# B_UN_C.net
KiCad netlist of a schematic drawn in Altium Designer
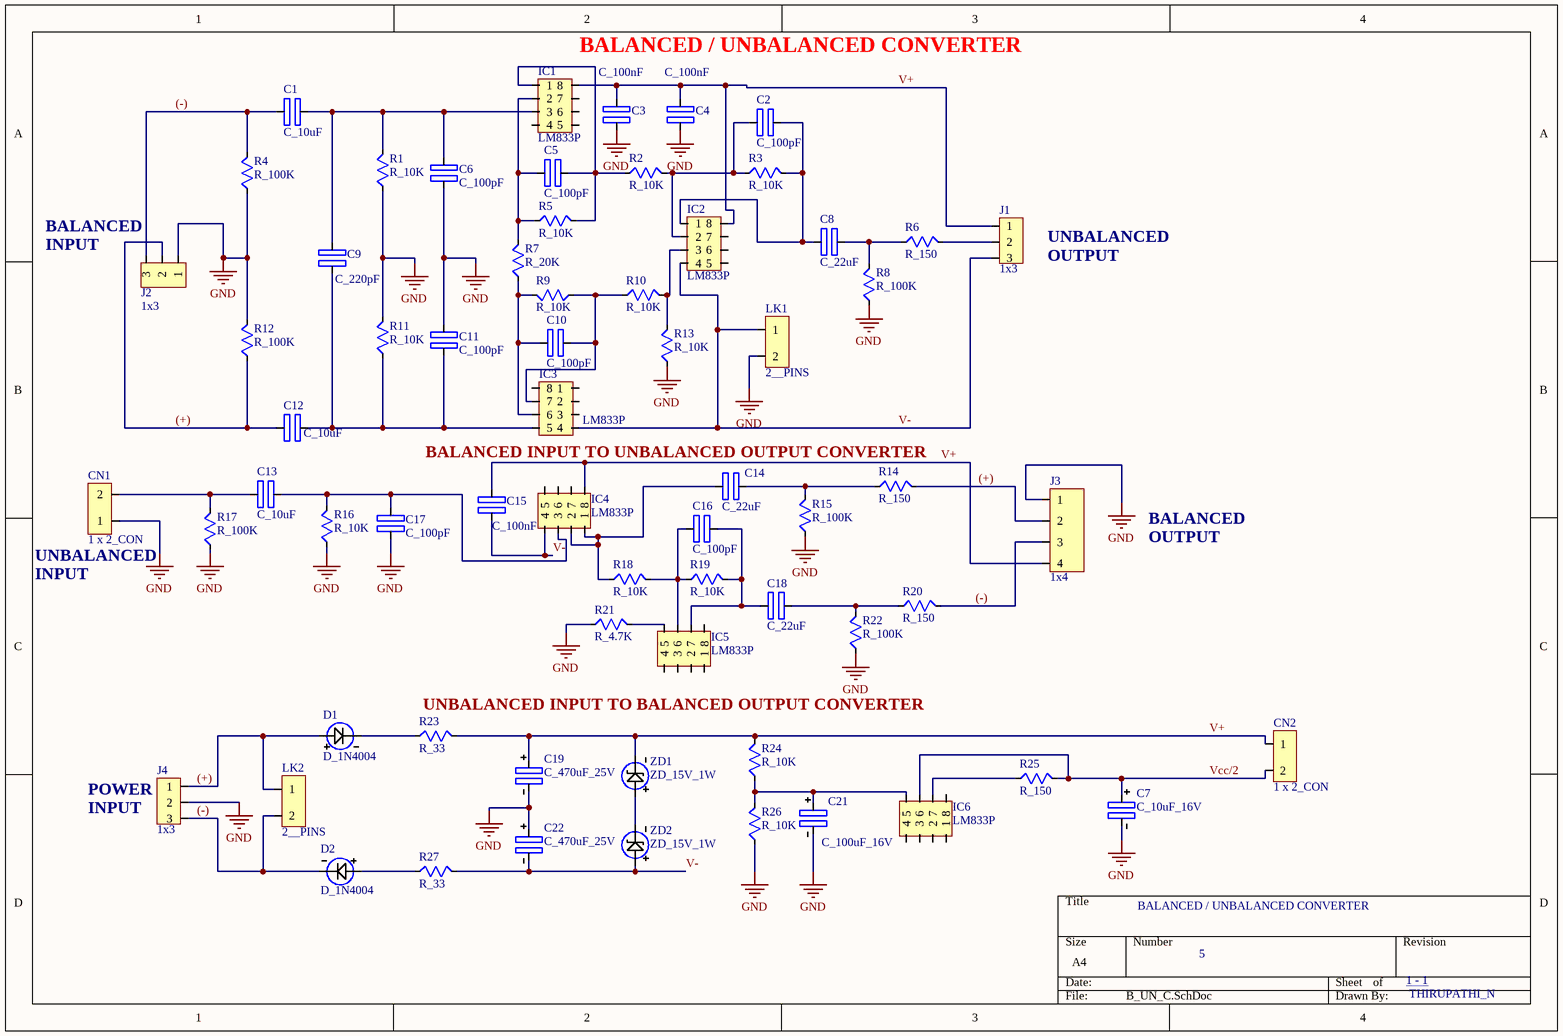
[diagram p0: B_UN_C.SchDoc]

(export (version "E")
  (design (tool "Eeschema 10.0.6"))
  (components
    (comp (ref "C1")
      (value "C_10uF")
      (footprint "C_10uF")
      (description "CAP ALUM 10UF 20% 400V RADIAL")
      (fields
        (field (name "MANUFACTURER") "Nichicon")
        (field (name "MANUFACTURER PART NUMBER") "UCA2G100MPD1TD")
      )
      (libsource (lib "Schlib1") (part "C_10uF"))
    )
    (comp (ref "C2")
      (value "C_100pF")
      (footprint "C_100pF")
      (description "CAPACITOR CERAMIC 100PF 3000V C0G 5%, RAD")
      (fields
        (field (name "MANUFACTURER") "KEMET")
        (field (name "MANUFACTURER PART NUMBER") "C330C101JHG5TA")
      )
      (libsource (lib "Schlib1") (part "C_100pF"))
    )
    (comp (ref "C3")
      (value "C_100nF")
      (footprint "C_100nF")
      (description "NICHICON   UVR2A0R1MDD1TD   ALUMINUM ELECTROLYTIC CAPACITOR, 0.1UF, 100V, 20%, RADIAL")
      (fields
        (field (name "MANUFACTURER") "Nichicon")
        (field (name "MANUFACTURER PART NUMBER") "UVR2A0R1MDD1TD")
      )
      (libsource (lib "Schlib1") (part "C_100nF"))
    )
    (comp (ref "C4")
      (value "C_100nF")
      (footprint "C_100nF")
      (description "NICHICON   UVR2A0R1MDD1TD   ALUMINUM ELECTROLYTIC CAPACITOR, 0.1UF, 100V, 20%, RADIAL")
      (fields
        (field (name "MANUFACTURER") "Nichicon")
        (field (name "MANUFACTURER PART NUMBER") "UVR2A0R1MDD1TD")
      )
      (libsource (lib "Schlib1") (part "C_100nF"))
    )
    (comp (ref "C5")
      (value "C_100pF")
      (footprint "C_100pF")
      (description "CAPACITOR CERAMIC 100PF 3000V C0G 5%, RAD")
      (fields
        (field (name "MANUFACTURER") "KEMET")
        (field (name "MANUFACTURER PART NUMBER") "C330C101JHG5TA")
      )
      (libsource (lib "Schlib1") (part "C_100pF"))
    )
    (comp (ref "C6")
      (value "C_100pF")
      (footprint "C_100pF")
      (description "CAPACITOR CERAMIC 100PF 3000V C0G 5%, RAD")
      (fields
        (field (name "MANUFACTURER") "KEMET")
        (field (name "MANUFACTURER PART NUMBER") "C330C101JHG5TA")
      )
      (libsource (lib "Schlib1") (part "C_100pF"))
    )
    (comp (ref "C7")
      (value "C_10uF_16V")
      (footprint "C_10uF_16V")
      (description "CAPACITOR ALUM ELECT, 10UF, 16V, 20%, RADIAL")
      (fields
        (field (name "MANUFACTURER") "Nichicon")
        (field (name "MANUFACTURER PART NUMBER") "UST1C100MDD1TE")
      )
      (libsource (lib "Schlib1") (part "C_10uF_16V"))
    )
    (comp (ref "C8")
      (value "C_22uF")
      (footprint "C_22uF")
      (description "Cap Aluminum Lytic 22uF 50V 20% (5 X 11mm) Radial 2.5mm 95mA 2000h 85C Ammo Pack")
      (fields
        (field (name "MANUFACTURER") "Nichicon")
        (field (name "MANUFACTURER PART NUMBER") "UVR1H220MDD1TD")
      )
      (libsource (lib "Schlib1") (part "C_22uF"))
    )
    (comp (ref "C9")
      (value "C_220pF")
      (footprint "C_220pF")
      (fields
        (field (name "MANUFACTURER") "Vishay BCcomponents")
        (field (name "MANUFACTURER PART NUMBER") "F221K25Y5RN6UK5R")
        (field (name "TOLERANCE") "10%")
      )
      (libsource (lib "Schlib1") (part "C_220pF"))
    )
    (comp (ref "C10")
      (value "C_100pF")
      (footprint "C_100pF")
      (description "CAPACITOR CERAMIC 100PF 3000V C0G 5%, RAD")
      (fields
        (field (name "MANUFACTURER") "KEMET")
        (field (name "MANUFACTURER PART NUMBER") "C330C101JHG5TA")
      )
      (libsource (lib "Schlib1") (part "C_100pF"))
    )
    (comp (ref "C11")
      (value "C_100pF")
      (footprint "C_100pF")
      (description "CAPACITOR CERAMIC 100PF 3000V C0G 5%, RAD")
      (fields
        (field (name "MANUFACTURER") "KEMET")
        (field (name "MANUFACTURER PART NUMBER") "C330C101JHG5TA")
      )
      (libsource (lib "Schlib1") (part "C_100pF"))
    )
    (comp (ref "C12")
      (value "C_10uF")
      (footprint "C_10uF")
      (description "CAP ALUM 10UF 20% 400V RADIAL")
      (fields
        (field (name "MANUFACTURER") "Nichicon")
        (field (name "MANUFACTURER PART NUMBER") "UCA2G100MPD1TD")
      )
      (libsource (lib "Schlib1") (part "C_10uF"))
    )
    (comp (ref "C13")
      (value "C_10uF")
      (footprint "C_10uF")
      (description "CAP ALUM 10UF 20% 400V RADIAL")
      (fields
        (field (name "MANUFACTURER") "Nichicon")
        (field (name "MANUFACTURER PART NUMBER") "UCA2G100MPD1TD")
      )
      (libsource (lib "Schlib1") (part "C_10uF"))
    )
    (comp (ref "C14")
      (value "C_22uF")
      (footprint "C_22uF")
      (description "Cap Aluminum Lytic 22uF 50V 20% (5 X 11mm) Radial 2.5mm 95mA 2000h 85C Ammo Pack")
      (fields
        (field (name "MANUFACTURER") "Nichicon")
        (field (name "MANUFACTURER PART NUMBER") "UVR1H220MDD1TD")
      )
      (libsource (lib "Schlib1") (part "C_22uF"))
    )
    (comp (ref "C15")
      (value "C_100nF")
      (footprint "C_100nF")
      (description "NICHICON   UVR2A0R1MDD1TD   ALUMINUM ELECTROLYTIC CAPACITOR, 0.1UF, 100V, 20%, RADIAL")
      (fields
        (field (name "MANUFACTURER") "Nichicon")
        (field (name "MANUFACTURER PART NUMBER") "UVR2A0R1MDD1TD")
      )
      (libsource (lib "Schlib1") (part "C_100nF"))
    )
    (comp (ref "C16")
      (value "C_100pF")
      (footprint "C_100pF")
      (description "CAPACITOR CERAMIC 100PF 3000V C0G 5%, RAD")
      (fields
        (field (name "MANUFACTURER") "KEMET")
        (field (name "MANUFACTURER PART NUMBER") "C330C101JHG5TA")
      )
      (libsource (lib "Schlib1") (part "C_100pF"))
    )
    (comp (ref "C17")
      (value "C_100pF")
      (footprint "C_100pF")
      (description "CAPACITOR CERAMIC 100PF 3000V C0G 5%, RAD")
      (fields
        (field (name "MANUFACTURER") "KEMET")
        (field (name "MANUFACTURER PART NUMBER") "C330C101JHG5TA")
      )
      (libsource (lib "Schlib1") (part "C_100pF"))
    )
    (comp (ref "C18")
      (value "C_22uF")
      (footprint "C_22uF")
      (description "Cap Aluminum Lytic 22uF 50V 20% (5 X 11mm) Radial 2.5mm 95mA 2000h 85C Ammo Pack")
      (fields
        (field (name "MANUFACTURER") "Nichicon")
        (field (name "MANUFACTURER PART NUMBER") "UVR1H220MDD1TD")
      )
      (libsource (lib "Schlib1") (part "C_22uF"))
    )
    (comp (ref "C19")
      (value "C_470uF_25V")
      (footprint "C_25V_470uF")
      (fields
        (field (name "MANUFACTURER") "Nichicon")
        (field (name "MANUFACTURER PART NUMBER") "UHE1E471MPD6TD")
        (field (name "TOLERANCE") "20%")
      )
      (libsource (lib "Schlib1") (part "C_470uF_25V"))
    )
    (comp (ref "C21")
      (value "C_100uF_16V")
      (footprint "C_100uF_16V")
      (description "Cap Aluminum Lytic 100uF 16V 20% (6.3 X 7mm) Radial 2.5mm 110mA 1000h 105°C Ammo")
      (fields
        (field (name "MANUFACTURER") "KEMET")
        (field (name "MANUFACTURER PART NUMBER") "ESS107M016AE2EA")
      )
      (libsource (lib "Schlib1") (part "C_100uF_16V"))
    )
    (comp (ref "C22")
      (value "C_470uF_25V")
      (footprint "C_25V_470uF")
      (fields
        (field (name "MANUFACTURER") "Nichicon")
        (field (name "MANUFACTURER PART NUMBER") "UHE1E471MPD6TD")
        (field (name "TOLERANCE") "20%")
      )
      (libsource (lib "Schlib1") (part "C_470uF_25V"))
    )
    (comp (ref "CN1")
      (value "1 x 2_CON")
      (footprint "1*2_CONNECTOR")
      (description "TERM BLK 2POS SIDE ENTRY 5MM PCB")
      (fields
        (field (name "MANUFACTURER") "Wurth Electronics")
        (field (name "MANUFACTURER PART NUMBER") "691137710002")
      )
      (libsource (lib "") (part "1 x 2_CON_1"))
    )
    (comp (ref "CN2")
      (value "1 x 2_CON")
      (footprint "1*2_CONNECTOR")
      (description "TERM BLK 2POS SIDE ENTRY 5MM PCB")
      (fields
        (field (name "MANUFACTURER") "Wurth Electronics")
        (field (name "MANUFACTURER PART NUMBER") "691137710002")
      )
      (libsource (lib "Schlib1") (part "1 x 2_CON"))
    )
    (comp (ref "D1")
      (value "D_1N4004")
      (footprint "D_IN4004")
      (description "DIODES INC. - 1N4004-T - Standard Recovery Diode, 400 V, 1 A, Single, 1 V, 30 A")
      (fields (field (name "MANUFACTURER") "Diodes") (field (name "MANUFACTURER PART NUMBER") "1N4004-T"))
      (libsource (lib "Schlib1") (part "D_1N4004"))
    )
    (comp (ref "D2")
      (value "D_1N4004")
      (footprint "D_IN4004")
      (description "DIODES INC. - 1N4004-T - Standard Recovery Diode, 400 V, 1 A, Single, 1 V, 30 A")
      (fields (field (name "MANUFACTURER") "Diodes") (field (name "MANUFACTURER PART NUMBER") "1N4004-T"))
      (libsource (lib "Schlib1") (part "D_1N4004"))
    )
    (comp (ref "IC1")
      (value "LM833P")
      (footprint "IC_833")
      (description "OP Amp Dual GP 18V/36V 8-Pin PDIP Tube")
      (fields (field (name "MANUFACTURER") "Texas Instruments"))
      (libsource (lib "Schlib1") (part "LM833P"))
    )
    (comp (ref "IC2")
      (value "LM833P")
      (footprint "IC_833")
      (description "OP Amp Dual GP 18V/36V 8-Pin PDIP Tube")
      (fields (field (name "MANUFACTURER") "Texas Instruments"))
      (libsource (lib "Schlib1") (part "LM833P"))
    )
    (comp (ref "IC3")
      (value "LM833P")
      (footprint "IC_833")
      (description "OP Amp Dual GP 18V/36V 8-Pin PDIP Tube")
      (fields (field (name "MANUFACTURER") "Texas Instruments"))
      (libsource (lib "") (part "LM833P_1"))
    )
    (comp (ref "IC4")
      (value "LM833P")
      (footprint "IC_833")
      (description "OP Amp Dual GP 18V/36V 8-Pin PDIP Tube")
      (fields (field (name "MANUFACTURER") "Texas Instruments"))
      (libsource (lib "Schlib1") (part "LM833P"))
    )
    (comp (ref "IC5")
      (value "LM833P")
      (footprint "IC_833")
      (description "OP Amp Dual GP 18V/36V 8-Pin PDIP Tube")
      (fields (field (name "MANUFACTURER") "Texas Instruments"))
      (libsource (lib "Schlib1") (part "LM833P"))
    )
    (comp (ref "IC6")
      (value "LM833P")
      (footprint "IC_833")
      (description "OP Amp Dual GP 18V/36V 8-Pin PDIP Tube")
      (fields (field (name "MANUFACTURER") "Texas Instruments"))
      (libsource (lib "Schlib1") (part "LM833P"))
    )
    (comp (ref "J1")
      (value "1x3")
      (footprint "1*3_CONNECTOR")
      (description "Fixed Terminal Blocks WR-TBL SMT Model7097 3Pin 5mm Hztl")
      (fields
        (field (name "MANUFACTURER") "Wurth Electronics Midcom")
        (field (name "MANUFACTURER PART NUMBER") "691709710303")
      )
      (libsource (lib "Schlib1") (part "1x3"))
    )
    (comp (ref "J2")
      (value "1x3")
      (footprint "1*3_CONNECTOR")
      (description "Fixed Terminal Blocks WR-TBL SMT Model7097 3Pin 5mm Hztl")
      (fields
        (field (name "MANUFACTURER") "Wurth Electronics Midcom")
        (field (name "MANUFACTURER PART NUMBER") "691709710303")
      )
      (libsource (lib "") (part "1x3_1"))
    )
    (comp (ref "J3")
      (value "1x4")
      (footprint "1*4_CONNECTOR")
      (description "TERM BLK 4POS SIDE ENTRY 5MM PCB")
      (fields
        (field (name "MANUFACTURER") "Wurth Electronics")
        (field (name "MANUFACTURER PART NUMBER") "691137710004")
      )
      (libsource (lib "Schlib1") (part "1x4"))
    )
    (comp (ref "J4")
      (value "1x3")
      (footprint "1*3_CONNECTOR")
      (description "Fixed Terminal Blocks WR-TBL SMT Model7097 3Pin 5mm Hztl")
      (fields
        (field (name "MANUFACTURER") "Wurth Electronics Midcom")
        (field (name "MANUFACTURER PART NUMBER") "691709710303")
      )
      (libsource (lib "") (part "1x3_1"))
    )
    (comp (ref "LK1")
      (value "2__PINS")
      (footprint "2_PIN")
      (description "HARWIN - M20-9990246 - CONNECTOR, HEADER, 2 POSITION, 1ROW, 2.54MM")
      (fields (field (name "MANUFACTURER") "Harwin") (field (name "MANUFACTURER PART NUMBER") "M20-9990246"))
      (libsource (lib "Schlib1") (part "2__PINS"))
    )
    (comp (ref "LK2")
      (value "2__PINS")
      (footprint "2_PIN")
      (description "HARWIN - M20-9990246 - CONNECTOR, HEADER, 2 POSITION, 1ROW, 2.54MM")
      (fields (field (name "MANUFACTURER") "Harwin") (field (name "MANUFACTURER PART NUMBER") "M20-9990246"))
      (libsource (lib "Schlib1") (part "2__PINS"))
    )
    (comp (ref "R1")
      (value "R_10K")
      (footprint "CF_RESISTOR_FP")
      (description "RES 10K OHM 1/4W 5% AXIAL")
      (fields
        (field (name "MANUFACTURER") "Stackpole Electronics")
        (field (name "MANUFACTURER PART NUMBER") "CF14JT10K0")
      )
      (libsource (lib "Schlib1") (part "R_10K"))
    )
    (comp (ref "R2")
      (value "R_10K")
      (footprint "CF_RESISTOR_FP")
      (description "RES 10K OHM 1/4W 5% AXIAL")
      (fields
        (field (name "MANUFACTURER") "Stackpole Electronics")
        (field (name "MANUFACTURER PART NUMBER") "CF14JT10K0")
      )
      (libsource (lib "Schlib1") (part "R_10K"))
    )
    (comp (ref "R3")
      (value "R_10K")
      (footprint "CF_RESISTOR_FP")
      (description "RES 10K OHM 1/4W 5% AXIAL")
      (fields
        (field (name "MANUFACTURER") "Stackpole Electronics")
        (field (name "MANUFACTURER PART NUMBER") "CF14JT10K0")
      )
      (libsource (lib "Schlib1") (part "R_10K"))
    )
    (comp (ref "R4")
      (value "R_100K")
      (footprint "CF_RESISTOR_FP")
      (description "RES 100K OHM 1/4W 5% AXIAL")
      (fields
        (field (name "MANUFACTURER") "Stackpole Electronics")
        (field (name "MANUFACTURER PART NUMBER") "CF14JT100K")
      )
      (libsource (lib "Schlib1") (part "R_100K"))
    )
    (comp (ref "R5")
      (value "R_10K")
      (footprint "CF_RESISTOR_FP")
      (description "RES 10K OHM 1/4W 5% AXIAL")
      (fields
        (field (name "MANUFACTURER") "Stackpole Electronics")
        (field (name "MANUFACTURER PART NUMBER") "CF14JT10K0")
      )
      (libsource (lib "Schlib1") (part "R_10K"))
    )
    (comp (ref "R6")
      (value "R_150")
      (footprint "CF_RESISTOR_FP")
      (description "Res Carbon Film 150 Ohm 5% 1/4W -400ppm/C to 0ppm/C Conformal AXL Thru-Hole T/R")
      (fields
        (field (name "MANUFACTURER") "Stackpole Electronics")
        (field (name "MANUFACTURER PART NUMBER") "CF14JT150R")
      )
      (libsource (lib "Schlib1") (part "R_150"))
    )
    (comp (ref "R7")
      (value "R_20K")
      (footprint "CF_RESISTOR_FP")
      (description "RES 20K OHM 1/2W 5% AXIAL")
      (fields
        (field (name "MANUFACTURER") "Stackpole Electronics")
        (field (name "MANUFACTURER PART NUMBER") "CF12JT20K0")
      )
      (libsource (lib "Schlib1") (part "R_20K"))
    )
    (comp (ref "R8")
      (value "R_100K")
      (footprint "CF_RESISTOR_FP")
      (description "RES 100K OHM 1/4W 5% AXIAL")
      (fields
        (field (name "MANUFACTURER") "Stackpole Electronics")
        (field (name "MANUFACTURER PART NUMBER") "CF14JT100K")
      )
      (libsource (lib "Schlib1") (part "R_100K"))
    )
    (comp (ref "R9")
      (value "R_10K")
      (footprint "CF_RESISTOR_FP")
      (description "RES 10K OHM 1/4W 5% AXIAL")
      (fields
        (field (name "MANUFACTURER") "Stackpole Electronics")
        (field (name "MANUFACTURER PART NUMBER") "CF14JT10K0")
      )
      (libsource (lib "Schlib1") (part "R_10K"))
    )
    (comp (ref "R10")
      (value "R_10K")
      (footprint "CF_RESISTOR_FP")
      (description "RES 10K OHM 1/4W 5% AXIAL")
      (fields
        (field (name "MANUFACTURER") "Stackpole Electronics")
        (field (name "MANUFACTURER PART NUMBER") "CF14JT10K0")
      )
      (libsource (lib "Schlib1") (part "R_10K"))
    )
    (comp (ref "R11")
      (value "R_10K")
      (footprint "CF_RESISTOR_FP")
      (description "RES 10K OHM 1/4W 5% AXIAL")
      (fields
        (field (name "MANUFACTURER") "Stackpole Electronics")
        (field (name "MANUFACTURER PART NUMBER") "CF14JT10K0")
      )
      (libsource (lib "Schlib1") (part "R_10K"))
    )
    (comp (ref "R12")
      (value "R_100K")
      (footprint "CF_RESISTOR_FP")
      (description "RES 100K OHM 1/4W 5% AXIAL")
      (fields
        (field (name "MANUFACTURER") "Stackpole Electronics")
        (field (name "MANUFACTURER PART NUMBER") "CF14JT100K")
      )
      (libsource (lib "Schlib1") (part "R_100K"))
    )
    (comp (ref "R13")
      (value "R_10K")
      (footprint "CF_RESISTOR_FP")
      (description "RES 10K OHM 1/4W 5% AXIAL")
      (fields
        (field (name "MANUFACTURER") "Stackpole Electronics")
        (field (name "MANUFACTURER PART NUMBER") "CF14JT10K0")
      )
      (libsource (lib "Schlib1") (part "R_10K"))
    )
    (comp (ref "R14")
      (value "R_150")
      (footprint "CF_RESISTOR_FP")
      (description "Res Carbon Film 150 Ohm 5% 1/4W -400ppm/C to 0ppm/C Conformal AXL Thru-Hole T/R")
      (fields
        (field (name "MANUFACTURER") "Stackpole Electronics")
        (field (name "MANUFACTURER PART NUMBER") "CF14JT150R")
      )
      (libsource (lib "Schlib1") (part "R_150"))
    )
    (comp (ref "R15")
      (value "R_100K")
      (footprint "CF_RESISTOR_FP")
      (description "RES 100K OHM 1/4W 5% AXIAL")
      (fields
        (field (name "MANUFACTURER") "Stackpole Electronics")
        (field (name "MANUFACTURER PART NUMBER") "CF14JT100K")
      )
      (libsource (lib "Schlib1") (part "R_100K"))
    )
    (comp (ref "R16")
      (value "R_10K")
      (footprint "CF_RESISTOR_FP")
      (description "RES 10K OHM 1/4W 5% AXIAL")
      (fields
        (field (name "MANUFACTURER") "Stackpole Electronics")
        (field (name "MANUFACTURER PART NUMBER") "CF14JT10K0")
      )
      (libsource (lib "Schlib1") (part "R_10K"))
    )
    (comp (ref "R17")
      (value "R_100K")
      (footprint "CF_RESISTOR_FP")
      (description "RES 100K OHM 1/4W 5% AXIAL")
      (fields
        (field (name "MANUFACTURER") "Stackpole Electronics")
        (field (name "MANUFACTURER PART NUMBER") "CF14JT100K")
      )
      (libsource (lib "Schlib1") (part "R_100K"))
    )
    (comp (ref "R18")
      (value "R_10K")
      (footprint "CF_RESISTOR_FP")
      (description "RES 10K OHM 1/4W 5% AXIAL")
      (fields
        (field (name "MANUFACTURER") "Stackpole Electronics")
        (field (name "MANUFACTURER PART NUMBER") "CF14JT10K0")
      )
      (libsource (lib "Schlib1") (part "R_10K"))
    )
    (comp (ref "R19")
      (value "R_10K")
      (footprint "CF_RESISTOR_FP")
      (description "RES 10K OHM 1/4W 5% AXIAL")
      (fields
        (field (name "MANUFACTURER") "Stackpole Electronics")
        (field (name "MANUFACTURER PART NUMBER") "CF14JT10K0")
      )
      (libsource (lib "Schlib1") (part "R_10K"))
    )
    (comp (ref "R20")
      (value "R_150")
      (footprint "CF_RESISTOR_FP")
      (description "Res Carbon Film 150 Ohm 5% 1/4W -400ppm/C to 0ppm/C Conformal AXL Thru-Hole T/R")
      (fields
        (field (name "MANUFACTURER") "Stackpole Electronics")
        (field (name "MANUFACTURER PART NUMBER") "CF14JT150R")
      )
      (libsource (lib "Schlib1") (part "R_150"))
    )
    (comp (ref "R21")
      (value "R_4.7K")
      (footprint "R_4.7K")
      (fields
        (field (name "MANUFACTURER") "Ohmite")
        (field (name "MANUFACTURER PART NUMBER") "OY472KE")
        (field (name "TOLERANCE") "10%")
      )
      (libsource (lib "Schlib1") (part "R_4.7K"))
    )
    (comp (ref "R22")
      (value "R_100K")
      (footprint "CF_RESISTOR_FP")
      (description "RES 100K OHM 1/4W 5% AXIAL")
      (fields
        (field (name "MANUFACTURER") "Stackpole Electronics")
        (field (name "MANUFACTURER PART NUMBER") "CF14JT100K")
      )
      (libsource (lib "Schlib1") (part "R_100K"))
    )
    (comp (ref "R23")
      (value "R_33")
      (footprint "CF_RESISTOR_FP")
      (description "RES 33 OHM 1/2W 5% AXIAL")
      (fields
        (field (name "MANUFACTURER") "Stackpole Electronics")
        (field (name "MANUFACTURER PART NUMBER") "CF12JT33R0")
      )
      (libsource (lib "Schlib1") (part "R_33"))
    )
    (comp (ref "R24")
      (value "R_10K")
      (footprint "CF_RESISTOR_FP")
      (description "RES 10K OHM 1/4W 5% AXIAL")
      (fields
        (field (name "MANUFACTURER") "Stackpole Electronics")
        (field (name "MANUFACTURER PART NUMBER") "CF14JT10K0")
      )
      (libsource (lib "Schlib1") (part "R_10K"))
    )
    (comp (ref "R25")
      (value "R_150")
      (footprint "CF_RESISTOR_FP")
      (description "Res Carbon Film 150 Ohm 5% 1/4W -400ppm/C to 0ppm/C Conformal AXL Thru-Hole T/R")
      (fields
        (field (name "MANUFACTURER") "Stackpole Electronics")
        (field (name "MANUFACTURER PART NUMBER") "CF14JT150R")
      )
      (libsource (lib "Schlib1") (part "R_150"))
    )
    (comp (ref "R26")
      (value "R_10K")
      (footprint "CF_RESISTOR_FP")
      (description "RES 10K OHM 1/4W 5% AXIAL")
      (fields
        (field (name "MANUFACTURER") "Stackpole Electronics")
        (field (name "MANUFACTURER PART NUMBER") "CF14JT10K0")
      )
      (libsource (lib "Schlib1") (part "R_10K"))
    )
    (comp (ref "R27")
      (value "R_33")
      (footprint "CF_RESISTOR_FP")
      (description "RES 33 OHM 1/2W 5% AXIAL")
      (fields
        (field (name "MANUFACTURER") "Stackpole Electronics")
        (field (name "MANUFACTURER PART NUMBER") "CF12JT33R0")
      )
      (libsource (lib "Schlib1") (part "R_33"))
    )
    (comp (ref "ZD1")
      (value "ZD_15V_1W")
      (footprint "ZR_15V_1W")
      (description "GLOVE, POLYAMIDE, L/FREE, PU, SIZE 6 - More Details")
      (fields
        (field (name "MANUFACTURER") "NXP Semiconductors")
        (field (name "MANUFACTURER PART NUMBER") "BZV85-C15,113")
      )
      (libsource (lib "Schlib1") (part "ZD_15V_1W"))
    )
    (comp (ref "ZD2")
      (value "ZD_15V_1W")
      (footprint "ZR_15V_1W")
      (description "GLOVE, POLYAMIDE, L/FREE, PU, SIZE 6 - More Details")
      (fields
        (field (name "MANUFACTURER") "NXP Semiconductors")
        (field (name "MANUFACTURER PART NUMBER") "BZV85-C15,113")
      )
      (libsource (lib "Schlib1") (part "ZD_15V_1W"))
    )
  )
  (nets
    (net (code "1") (name "/(+)") (class "Default")
      (node (ref "C12") (pin "0") (pinfunction "0_0") (pintype "passive"))
      (node (ref "D1") (pin "2") (pinfunction "2_2") (pintype "passive"))
      (node (ref "J2") (pin "2") (pinfunction "2_2") (pintype "passive"))
      (node (ref "J3") (pin "2") (pinfunction "2_2") (pintype "passive"))
      (node (ref "J4") (pin "1") (pinfunction "1_1") (pintype "passive"))
      (node (ref "LK2") (pin "1") (pinfunction "1_1") (pintype "passive"))
      (node (ref "R12") (pin "0") (pinfunction "0_0") (pintype "passive"))
      (node (ref "R14") (pin "1") (pinfunction "1_1") (pintype "passive"))
    )
    (net (code "2") (name "/(-)") (class "Default")
      (node (ref "C1") (pin "0") (pinfunction "0_0") (pintype "passive"))
      (node (ref "D2") (pin "1") (pinfunction "1_1") (pintype "passive"))
      (node (ref "J2") (pin "3") (pinfunction "3_3") (pintype "passive"))
      (node (ref "J3") (pin "3") (pinfunction "3_3") (pintype "passive"))
      (node (ref "J4") (pin "3") (pinfunction "3_3") (pintype "passive"))
      (node (ref "LK2") (pin "2") (pinfunction "2_2") (pintype "passive"))
      (node (ref "R20") (pin "1") (pinfunction "1_1") (pintype "passive"))
      (node (ref "R4") (pin "1") (pinfunction "1_1") (pintype "passive"))
    )
    (net (code "3") (name "/V+") (class "Default")
      (node (ref "C15") (pin "1") (pinfunction "1_1") (pintype "passive"))
      (node (ref "C19") (pin "0") (pinfunction "0_0") (pintype "passive"))
      (node (ref "C3") (pin "1") (pinfunction "1_1") (pintype "passive"))
      (node (ref "C4") (pin "1") (pinfunction "1_1") (pintype "passive"))
      (node (ref "CN2") (pin "1") (pinfunction "1_1") (pintype "passive"))
      (node (ref "IC1") (pin "8") (pinfunction "8_8") (pintype "passive"))
      (node (ref "IC2") (pin "8") (pinfunction "8_8") (pintype "passive"))
      (node (ref "IC4") (pin "8") (pinfunction "8_8") (pintype "passive"))
      (node (ref "J1") (pin "1") (pinfunction "1_1") (pintype "passive"))
      (node (ref "J3") (pin "4") (pinfunction "4_4") (pintype "passive"))
      (node (ref "R23") (pin "1") (pinfunction "1_1") (pintype "passive"))
      (node (ref "R24") (pin "1") (pinfunction "1_1") (pintype "passive"))
      (node (ref "ZD1") (pin "1") (pinfunction "1_1") (pintype "passive"))
    )
    (net (code "4") (name "/V-") (class "Default")
      (node (ref "C15") (pin "0") (pinfunction "0_0") (pintype "passive"))
      (node (ref "C22") (pin "1") (pinfunction "1_1") (pintype "passive"))
      (node (ref "IC2") (pin "4") (pinfunction "4_4") (pintype "passive"))
      (node (ref "IC3") (pin "4") (pinfunction "4_4") (pintype "passive"))
      (node (ref "IC4") (pin "4") (pinfunction "4_4") (pintype "passive"))
      (node (ref "J1") (pin "3") (pinfunction "3_3") (pintype "passive"))
      (node (ref "LK1") (pin "1") (pinfunction "1_1") (pintype "passive"))
      (node (ref "R27") (pin "1") (pinfunction "1_1") (pintype "passive"))
      (node (ref "ZD2") (pin "2") (pinfunction "2_2") (pintype "passive"))
    )
    (net (code "5") (name "/Vcc{slash}2") (class "Default")
      (node (ref "C7") (pin "0") (pinfunction "0_0") (pintype "passive"))
      (node (ref "CN2") (pin "2") (pinfunction "2_2") (pintype "passive"))
      (node (ref "IC6") (pin "6") (pinfunction "6_6") (pintype "passive"))
      (node (ref "R25") (pin "1") (pinfunction "1_1") (pintype "passive"))
    )
    (net (code "6") (name "GND") (class "Default")
      (node (ref "C11") (pin "1") (pinfunction "1_1") (pintype "passive"))
      (node (ref "C17") (pin "0") (pinfunction "0_0") (pintype "passive"))
      (node (ref "C19") (pin "1") (pinfunction "1_1") (pintype "passive"))
      (node (ref "C21") (pin "1") (pinfunction "1_1") (pintype "passive"))
      (node (ref "C22") (pin "0") (pinfunction "0_0") (pintype "passive"))
      (node (ref "C3") (pin "0") (pinfunction "0_0") (pintype "passive"))
      (node (ref "C4") (pin "0") (pinfunction "0_0") (pintype "passive"))
      (node (ref "C6") (pin "0") (pinfunction "0_0") (pintype "passive"))
      (node (ref "C7") (pin "1") (pinfunction "1_1") (pintype "passive"))
      (node (ref "CN1") (pin "1") (pinfunction "1_1") (pintype "passive"))
      (node (ref "J2") (pin "1") (pinfunction "1_1") (pintype "passive"))
      (node (ref "J3") (pin "1") (pinfunction "1_1") (pintype "passive"))
      (node (ref "J4") (pin "2") (pinfunction "2_2") (pintype "passive"))
      (node (ref "LK1") (pin "2") (pinfunction "2_2") (pintype "passive"))
      (node (ref "R1") (pin "0") (pinfunction "0_0") (pintype "passive"))
      (node (ref "R11") (pin "1") (pinfunction "1_1") (pintype "passive"))
      (node (ref "R12") (pin "1") (pinfunction "1_1") (pintype "passive"))
      (node (ref "R13") (pin "0") (pinfunction "0_0") (pintype "passive"))
      (node (ref "R15") (pin "0") (pinfunction "0_0") (pintype "passive"))
      (node (ref "R16") (pin "0") (pinfunction "0_0") (pintype "passive"))
      (node (ref "R17") (pin "0") (pinfunction "0_0") (pintype "passive"))
      (node (ref "R21") (pin "0") (pinfunction "0_0") (pintype "passive"))
      (node (ref "R22") (pin "0") (pinfunction "0_0") (pintype "passive"))
      (node (ref "R26") (pin "0") (pinfunction "0_0") (pintype "passive"))
      (node (ref "R4") (pin "0") (pinfunction "0_0") (pintype "passive"))
      (node (ref "R8") (pin "0") (pinfunction "0_0") (pintype "passive"))
    )
    (net (code "7") (name "Net-(C1-Pad1)") (class "Default")
      (node (ref "C1") (pin "1") (pinfunction "1_1") (pintype "passive"))
      (node (ref "C6") (pin "1") (pinfunction "1_1") (pintype "passive"))
      (node (ref "C9") (pin "1") (pinfunction "1_1") (pintype "passive"))
      (node (ref "IC1") (pin "3") (pinfunction "3_3") (pintype "passive"))
      (node (ref "R1") (pin "1") (pinfunction "1_1") (pintype "passive"))
    )
    (net (code "8") (name "Net-(C2-Pad0)") (class "Default")
      (node (ref "C2") (pin "0") (pinfunction "0_0") (pintype "passive"))
      (node (ref "IC2") (pin "2") (pinfunction "2_2") (pintype "passive"))
      (node (ref "R2") (pin "1") (pinfunction "1_1") (pintype "passive"))
      (node (ref "R3") (pin "0") (pinfunction "0_0") (pintype "passive"))
    )
    (net (code "9") (name "Net-(C2-Pad1)") (class "Default")
      (node (ref "C2") (pin "1") (pinfunction "1_1") (pintype "passive"))
      (node (ref "C8") (pin "0") (pinfunction "0_0") (pintype "passive"))
      (node (ref "IC2") (pin "1") (pinfunction "1_1") (pintype "passive"))
      (node (ref "R3") (pin "1") (pinfunction "1_1") (pintype "passive"))
    )
    (net (code "10") (name "Net-(C5-Pad0)") (class "Default")
      (node (ref "C5") (pin "0") (pinfunction "0_0") (pintype "passive"))
      (node (ref "IC1") (pin "2") (pinfunction "2_2") (pintype "passive"))
      (node (ref "R5") (pin "0") (pinfunction "0_0") (pintype "passive"))
      (node (ref "R7") (pin "1") (pinfunction "1_1") (pintype "passive"))
    )
    (net (code "11") (name "Net-(C5-Pad1)") (class "Default")
      (node (ref "C5") (pin "1") (pinfunction "1_1") (pintype "passive"))
      (node (ref "IC1") (pin "1") (pinfunction "1_1") (pintype "passive"))
      (node (ref "R2") (pin "0") (pinfunction "0_0") (pintype "passive"))
      (node (ref "R5") (pin "1") (pinfunction "1_1") (pintype "passive"))
    )
    (net (code "12") (name "Net-(C8-Pad1)") (class "Default")
      (node (ref "C8") (pin "1") (pinfunction "1_1") (pintype "passive"))
      (node (ref "R6") (pin "0") (pinfunction "0_0") (pintype "passive"))
      (node (ref "R8") (pin "1") (pinfunction "1_1") (pintype "passive"))
    )
    (net (code "13") (name "Net-(C10-Pad0)") (class "Default")
      (node (ref "C10") (pin "0") (pinfunction "0_0") (pintype "passive"))
      (node (ref "IC3") (pin "7") (pinfunction "7_7") (pintype "passive"))
      (node (ref "R10") (pin "0") (pinfunction "0_0") (pintype "passive"))
      (node (ref "R9") (pin "0") (pinfunction "0_0") (pintype "passive"))
    )
    (net (code "14") (name "Net-(C10-Pad1)") (class "Default")
      (node (ref "C10") (pin "1") (pinfunction "1_1") (pintype "passive"))
      (node (ref "IC3") (pin "6") (pinfunction "6_6") (pintype "passive"))
      (node (ref "R7") (pin "0") (pinfunction "0_0") (pintype "passive"))
      (node (ref "R9") (pin "1") (pinfunction "1_1") (pintype "passive"))
    )
    (net (code "15") (name "Net-(C11-Pad0)") (class "Default")
      (node (ref "C11") (pin "0") (pinfunction "0_0") (pintype "passive"))
      (node (ref "C12") (pin "1") (pinfunction "1_1") (pintype "passive"))
      (node (ref "C9") (pin "0") (pinfunction "0_0") (pintype "passive"))
      (node (ref "IC3") (pin "5") (pinfunction "5_5") (pintype "passive"))
      (node (ref "R11") (pin "0") (pinfunction "0_0") (pintype "passive"))
    )
    (net (code "16") (name "Net-(C13-Pad0)") (class "Default")
      (node (ref "C13") (pin "0") (pinfunction "0_0") (pintype "passive"))
      (node (ref "CN1") (pin "2") (pinfunction "2_2") (pintype "passive"))
      (node (ref "R17") (pin "1") (pinfunction "1_1") (pintype "passive"))
    )
    (net (code "17") (name "Net-(C13-Pad1)") (class "Default")
      (node (ref "C13") (pin "1") (pinfunction "1_1") (pintype "passive"))
      (node (ref "C17") (pin "1") (pinfunction "1_1") (pintype "passive"))
      (node (ref "IC4") (pin "3") (pinfunction "3_3") (pintype "passive"))
      (node (ref "R16") (pin "1") (pinfunction "1_1") (pintype "passive"))
    )
    (net (code "18") (name "Net-(C14-Pad0)") (class "Default")
      (node (ref "C14") (pin "0") (pinfunction "0_0") (pintype "passive"))
      (node (ref "IC4") (pin "1") (pinfunction "1_1") (pintype "passive"))
      (node (ref "IC4") (pin "2") (pinfunction "2_2") (pintype "passive"))
      (node (ref "R18") (pin "0") (pinfunction "0_0") (pintype "passive"))
    )
    (net (code "19") (name "Net-(C14-Pad1)") (class "Default")
      (node (ref "C14") (pin "1") (pinfunction "1_1") (pintype "passive"))
      (node (ref "R14") (pin "0") (pinfunction "0_0") (pintype "passive"))
      (node (ref "R15") (pin "1") (pinfunction "1_1") (pintype "passive"))
    )
    (net (code "20") (name "Net-(C16-Pad0)") (class "Default")
      (node (ref "C16") (pin "0") (pinfunction "0_0") (pintype "passive"))
      (node (ref "IC5") (pin "6") (pinfunction "6_6") (pintype "passive"))
      (node (ref "R18") (pin "1") (pinfunction "1_1") (pintype "passive"))
      (node (ref "R19") (pin "0") (pinfunction "0_0") (pintype "passive"))
    )
    (net (code "21") (name "Net-(C16-Pad1)") (class "Default")
      (node (ref "C16") (pin "1") (pinfunction "1_1") (pintype "passive"))
      (node (ref "C18") (pin "0") (pinfunction "0_0") (pintype "passive"))
      (node (ref "IC5") (pin "7") (pinfunction "7_7") (pintype "passive"))
      (node (ref "R19") (pin "1") (pinfunction "1_1") (pintype "passive"))
    )
    (net (code "22") (name "Net-(C18-Pad1)") (class "Default")
      (node (ref "C18") (pin "1") (pinfunction "1_1") (pintype "passive"))
      (node (ref "R20") (pin "0") (pinfunction "0_0") (pintype "passive"))
      (node (ref "R22") (pin "1") (pinfunction "1_1") (pintype "passive"))
    )
    (net (code "23") (name "Net-(C21-Pad0)") (class "Default")
      (node (ref "C21") (pin "0") (pinfunction "0_0") (pintype "passive"))
      (node (ref "IC6") (pin "5") (pinfunction "5_5") (pintype "passive"))
      (node (ref "R24") (pin "0") (pinfunction "0_0") (pintype "passive"))
      (node (ref "R26") (pin "1") (pinfunction "1_1") (pintype "passive"))
    )
    (net (code "24") (name "Net-(D1-Pad1)") (class "Default")
      (node (ref "D1") (pin "1") (pinfunction "1_1") (pintype "passive"))
      (node (ref "R23") (pin "0") (pinfunction "0_0") (pintype "passive"))
    )
    (net (code "25") (name "Net-(D2-Pad2)") (class "Default")
      (node (ref "D2") (pin "2") (pinfunction "2_2") (pintype "passive"))
      (node (ref "R27") (pin "0") (pinfunction "0_0") (pintype "passive"))
    )
    (net (code "26") (name "Net-(IC2-Pad3)") (class "Default")
      (node (ref "IC2") (pin "3") (pinfunction "3_3") (pintype "passive"))
      (node (ref "R10") (pin "1") (pinfunction "1_1") (pintype "passive"))
      (node (ref "R13") (pin "1") (pinfunction "1_1") (pintype "passive"))
    )
    (net (code "27") (name "Net-(IC5-Pad5)") (class "Default")
      (node (ref "IC5") (pin "5") (pinfunction "5_5") (pintype "passive"))
      (node (ref "R21") (pin "1") (pinfunction "1_1") (pintype "passive"))
    )
    (net (code "28") (name "Net-(IC6-Pad7)") (class "Default")
      (node (ref "IC6") (pin "7") (pinfunction "7_7") (pintype "passive"))
      (node (ref "R25") (pin "0") (pinfunction "0_0") (pintype "passive"))
    )
    (net (code "29") (name "Net-(J1-Pad2)") (class "Default")
      (node (ref "J1") (pin "2") (pinfunction "2_2") (pintype "passive"))
      (node (ref "R6") (pin "1") (pinfunction "1_1") (pintype "passive"))
    )
    (net (code "30") (name "Net-(ZD1-Pad2)") (class "Default")
      (node (ref "ZD1") (pin "2") (pinfunction "2_2") (pintype "passive"))
      (node (ref "ZD2") (pin "1") (pinfunction "1_1") (pintype "passive"))
    )
    (net (code "31") (name "unconnected-(IC1-Pad4)") (class "Default")
      (node (ref "IC1") (pin "4") (pinfunction "4_4") (pintype "passive"))
    )
    (net (code "32") (name "unconnected-(IC1-Pad5)") (class "Default")
      (node (ref "IC1") (pin "5") (pinfunction "5_5") (pintype "passive"))
    )
    (net (code "33") (name "unconnected-(IC1-Pad6)") (class "Default")
      (node (ref "IC1") (pin "6") (pinfunction "6_6") (pintype "passive"))
    )
    (net (code "34") (name "unconnected-(IC1-Pad7)") (class "Default")
      (node (ref "IC1") (pin "7") (pinfunction "7_7") (pintype "passive"))
    )
    (net (code "35") (name "unconnected-(IC2-Pad5)") (class "Default")
      (node (ref "IC2") (pin "5") (pinfunction "5_5") (pintype "passive"))
    )
    (net (code "36") (name "unconnected-(IC2-Pad6)") (class "Default")
      (node (ref "IC2") (pin "6") (pinfunction "6_6") (pintype "passive"))
    )
    (net (code "37") (name "unconnected-(IC2-Pad7)") (class "Default")
      (node (ref "IC2") (pin "7") (pinfunction "7_7") (pintype "passive"))
    )
    (net (code "38") (name "unconnected-(IC3-Pad1)") (class "Default")
      (node (ref "IC3") (pin "1") (pinfunction "1_1") (pintype "passive"))
    )
    (net (code "39") (name "unconnected-(IC3-Pad2)") (class "Default")
      (node (ref "IC3") (pin "2") (pinfunction "2_2") (pintype "passive"))
    )
    (net (code "40") (name "unconnected-(IC3-Pad3)") (class "Default")
      (node (ref "IC3") (pin "3") (pinfunction "3_3") (pintype "passive"))
    )
    (net (code "41") (name "unconnected-(IC3-Pad8)") (class "Default")
      (node (ref "IC3") (pin "8") (pinfunction "8_8") (pintype "passive"))
    )
    (net (code "42") (name "unconnected-(IC4-Pad5)") (class "Default")
      (node (ref "IC4") (pin "5") (pinfunction "5_5") (pintype "passive"))
    )
    (net (code "43") (name "unconnected-(IC4-Pad6)") (class "Default")
      (node (ref "IC4") (pin "6") (pinfunction "6_6") (pintype "passive"))
    )
    (net (code "44") (name "unconnected-(IC4-Pad7)") (class "Default")
      (node (ref "IC4") (pin "7") (pinfunction "7_7") (pintype "passive"))
    )
    (net (code "45") (name "unconnected-(IC5-Pad1)") (class "Default")
      (node (ref "IC5") (pin "1") (pinfunction "1_1") (pintype "passive"))
    )
    (net (code "46") (name "unconnected-(IC5-Pad2)") (class "Default")
      (node (ref "IC5") (pin "2") (pinfunction "2_2") (pintype "passive"))
    )
    (net (code "47") (name "unconnected-(IC5-Pad3)") (class "Default")
      (node (ref "IC5") (pin "3") (pinfunction "3_3") (pintype "passive"))
    )
    (net (code "48") (name "unconnected-(IC5-Pad4)") (class "Default")
      (node (ref "IC5") (pin "4") (pinfunction "4_4") (pintype "passive"))
    )
    (net (code "49") (name "unconnected-(IC5-Pad8)") (class "Default")
      (node (ref "IC5") (pin "8") (pinfunction "8_8") (pintype "passive"))
    )
    (net (code "50") (name "unconnected-(IC6-Pad1)") (class "Default")
      (node (ref "IC6") (pin "1") (pinfunction "1_1") (pintype "passive"))
    )
    (net (code "51") (name "unconnected-(IC6-Pad2)") (class "Default")
      (node (ref "IC6") (pin "2") (pinfunction "2_2") (pintype "passive"))
    )
    (net (code "52") (name "unconnected-(IC6-Pad3)") (class "Default")
      (node (ref "IC6") (pin "3") (pinfunction "3_3") (pintype "passive"))
    )
    (net (code "53") (name "unconnected-(IC6-Pad4)") (class "Default")
      (node (ref "IC6") (pin "4") (pinfunction "4_4") (pintype "passive"))
    )
    (net (code "54") (name "unconnected-(IC6-Pad8)") (class "Default")
      (node (ref "IC6") (pin "8") (pinfunction "8_8") (pintype "passive"))
    )
  )
)
